# Sheet1.net
KiCad netlist of a schematic drawn in Altium Designer
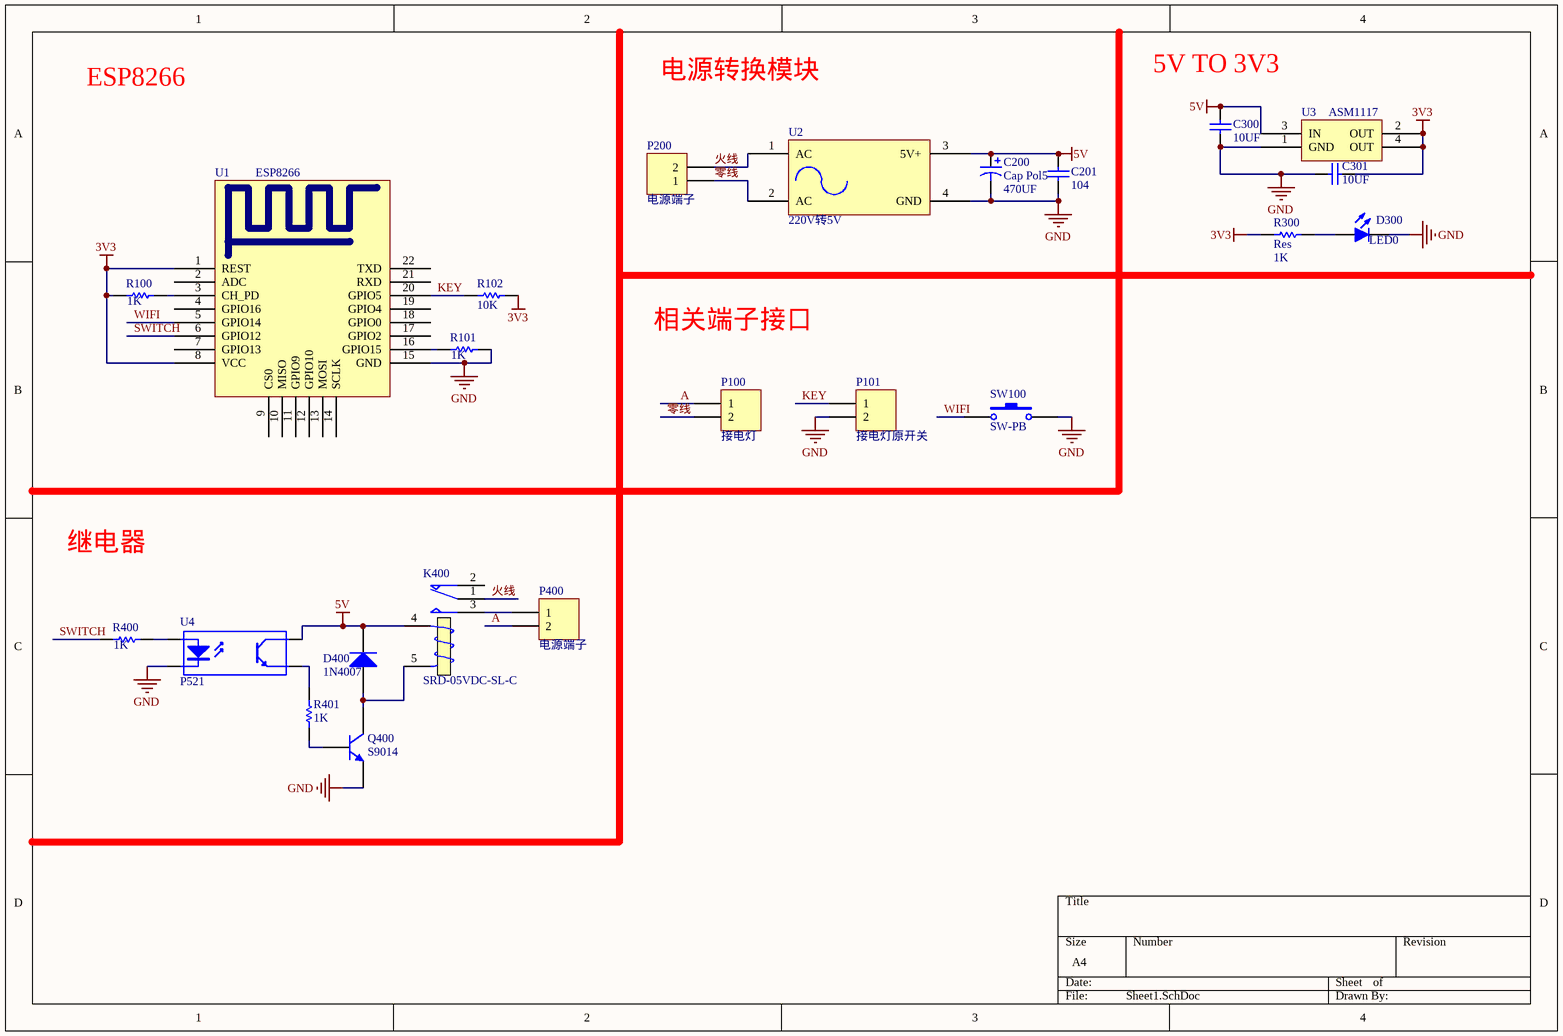
[diagram p0: Sheet1.SchDoc]

(export (version "E")
  (design (tool "Eeschema 10.0.6"))
  (components
    (comp (ref "C200")
      (value "Cap Pol5")
      (footprint "SMD8*10.5")
      (description "220UF电解电容")
      (fields (field (name "VAULE") "470UF"))
      (libsource (lib "myintlib") (part "Cap Pol5"))
    )
    (comp (ref "C201")
      (value "104")
      (footprint "Cap0805")
      (description "0805贴片电容")
      (libsource (lib "myintlib") (part "Cap"))
    )
    (comp (ref "C300")
      (value "10UF")
      (footprint "Cap0805")
      (description "0805贴片电容")
      (libsource (lib "myintlib") (part "Cap"))
    )
    (comp (ref "C301")
      (value "10UF")
      (footprint "Cap0805")
      (description "0805贴片电容")
      (libsource (lib "myintlib") (part "Cap"))
    )
    (comp (ref "D300")
      (value "LED0")
      (footprint "LED-0805")
      (description "0805贴片LED灯")
      (libsource (lib "myintlib") (part "LED0"))
    )
    (comp (ref "D400")
      (value "1N4007")
      (footprint "DO-214AA")
      (description "肖特基二极管")
      (libsource (lib "myintlib") (part "Doide"))
    )
    (comp (ref "K400")
      (value "SRD-05VDC-SL-C")
      (footprint "MODULE5B")
      (description "SPDT Relay")
      (fields (field (name "PUBLISHER") "Altium Limited"))
      (libsource (lib "Miscellaneous Devices") (part "Relay"))
    )
    (comp (ref "P100")
      (value "接电灯")
      (footprint "HDR1X2")
      (description "Header, 2-Pin")
      (fields (field (name "PUBLISHER") "Altium Limited"))
      (libsource (lib "Miscellaneous Connectors") (part "Header 2"))
    )
    (comp (ref "P101")
      (value "接电灯原开关")
      (footprint "HDR1X2")
      (description "Header, 2-Pin")
      (fields (field (name "PUBLISHER") "Altium Limited"))
      (libsource (lib "Miscellaneous Connectors") (part "Header 2"))
    )
    (comp (ref "P200")
      (value "电源端子")
      (footprint "HDR1X2")
      (description "Header, 2-Pin")
      (fields (field (name "PUBLISHER") "Altium Limited"))
      (libsource (lib "") (part "Header 2_1"))
    )
    (comp (ref "P400")
      (value "电源端子")
      (footprint "HDR1X2")
      (description "Header, 2-Pin")
      (fields (field (name "PUBLISHER") "Altium Limited"))
      (libsource (lib "Miscellaneous Connectors") (part "Header 2"))
    )
    (comp (ref "Q400")
      (value "S9014")
      (footprint "TO-226-AA")
      (description "NPN Bipolar Transistor")
      (fields (field (name "PUBLISHER") "Altium Limited"))
      (libsource (lib "Miscellaneous Devices") (part "NPN"))
    )
    (comp (ref "R100")
      (value "Res")
      (footprint "0805")
      (description "0805贴片电阻")
      (fields (field (name "VAULE") "1K"))
      (libsource (lib "myintlib") (part "Res"))
    )
    (comp (ref "R101")
      (value "Res")
      (footprint "0805")
      (description "0805贴片电阻")
      (fields (field (name "VAULE") "1K"))
      (libsource (lib "myintlib") (part "Res"))
    )
    (comp (ref "R102")
      (value "Res")
      (footprint "0805")
      (description "0805贴片电阻")
      (fields (field (name "VAULE") "10K"))
      (libsource (lib "myintlib") (part "Res"))
    )
    (comp (ref "R300")
      (value "Res")
      (footprint "0805")
      (description "0805贴片电阻")
      (fields (field (name "VAULE") "1K"))
      (libsource (lib "myintlib") (part "Res"))
    )
    (comp (ref "R400")
      (value "Res")
      (footprint "0805")
      (description "0805贴片电阻")
      (fields (field (name "VAULE") "1K"))
      (libsource (lib "myintlib") (part "Res"))
    )
    (comp (ref "R401")
      (value "Res")
      (footprint "0805")
      (description "0805贴片电阻")
      (fields (field (name "VAULE") "1K"))
      (libsource (lib "myintlib") (part "Res"))
    )
    (comp (ref "SW100")
      (value "SW-PB")
      (footprint "SW-PB")
      (description "贴片按键")
      (libsource (lib "myintlib") (part "SW-PB"))
    )
    (comp (ref "U1")
      (value "ESP8266")
      (footprint "ESP8266")
      (description "串口wifi模块")
      (libsource (lib "myintlib") (part "ESP8266"))
    )
    (comp (ref "U2") (value "220V转5V") (libsource (lib "myintlib") (part "电源转换")))
    (comp (ref "U3")
      (value "ASM1117")
      (footprint "SOT-223")
      (description "线性稳压芯片")
      (libsource (lib "myintlib") (part "ASM1117"))
    )
    (comp (ref "U4")
      (value "P521")
      (footprint "DIP-4")
      (description "4-Pin Phototransistor Optocoupler")
      (fields (field (name "PUBLISHER") "Altium Limited"))
      (libsource (lib "Miscellaneous Devices") (part "Optoisolator1"))
    )
  )
  (nets
    (net (code "1") (name "/A") (class "Default")
      (node (ref "P100") (pin "1") (pinfunction "1_1") (pintype "passive"))
      (node (ref "P400") (pin "2") (pinfunction "2_2") (pintype "passive"))
    )
    (net (code "2") (name "/KEY") (class "Default")
      (node (ref "P101") (pin "1") (pinfunction "1_1") (pintype "passive"))
      (node (ref "R102") (pin "1") (pinfunction "1_1") (pintype "passive"))
      (node (ref "U1") (pin "20") (pinfunction "GPIO5_20") (pintype "passive"))
    )
    (net (code "3") (name "/SWITCH") (class "Default")
      (node (ref "R400") (pin "1") (pinfunction "1_1") (pintype "passive"))
      (node (ref "U1") (pin "6") (pinfunction "GPIO12_6") (pintype "passive"))
    )
    (net (code "4") (name "/WIFI") (class "Default")
      (node (ref "SW100") (pin "1") (pinfunction "1_1") (pintype "passive"))
      (node (ref "U1") (pin "5") (pinfunction "GPIO14_5") (pintype "passive"))
    )
    (net (code "5") (name "/火线") (class "Default")
      (node (ref "K400") (pin "1") (pinfunction "COM_1") (pintype "passive"))
      (node (ref "P200") (pin "2") (pinfunction "2_2") (pintype "passive"))
      (node (ref "U2") (pin "1") (pinfunction "AC_1") (pintype "passive"))
    )
    (net (code "6") (name "/零线") (class "Default")
      (node (ref "P100") (pin "2") (pinfunction "2_2") (pintype "passive"))
      (node (ref "P200") (pin "1") (pinfunction "1_1") (pintype "passive"))
      (node (ref "U2") (pin "2") (pinfunction "AC_2") (pintype "passive"))
    )
    (net (code "7") (name "3V3") (class "Default")
      (node (ref "C301") (pin "1") (pinfunction "1_1") (pintype "passive"))
      (node (ref "R100") (pin "1") (pinfunction "1_1") (pintype "passive"))
      (node (ref "R102") (pin "2") (pinfunction "2_2") (pintype "passive"))
      (node (ref "R300") (pin "1") (pinfunction "1_1") (pintype "passive"))
      (node (ref "U1") (pin "1") (pinfunction "REST_1") (pintype "passive"))
      (node (ref "U1") (pin "8") (pinfunction "VCC_8") (pintype "passive"))
      (node (ref "U3") (pin "2") (pinfunction "OUT_2") (pintype "passive"))
      (node (ref "U3") (pin "4") (pinfunction "OUT_4") (pintype "passive"))
    )
    (net (code "8") (name "5V") (class "Default")
      (node (ref "C200") (pin "1") (pinfunction "1_1") (pintype "passive"))
      (node (ref "C201") (pin "1") (pinfunction "1_1") (pintype "passive"))
      (node (ref "C300") (pin "2") (pinfunction "2_2") (pintype "passive"))
      (node (ref "D400") (pin "2") (pinfunction "K_2") (pintype "passive"))
      (node (ref "K400") (pin "4") (pinfunction "T1_4") (pintype "passive"))
      (node (ref "U2") (pin "3") (pinfunction "5V+_3") (pintype "passive"))
      (node (ref "U3") (pin "3") (pinfunction "IN_3") (pintype "passive"))
      (node (ref "U4") (pin "4") (pinfunction "C_4") (pintype "passive"))
    )
    (net (code "9") (name "GND") (class "Default")
      (node (ref "C200") (pin "2") (pinfunction "2_2") (pintype "passive"))
      (node (ref "C201") (pin "2") (pinfunction "2_2") (pintype "passive"))
      (node (ref "C300") (pin "1") (pinfunction "1_1") (pintype "passive"))
      (node (ref "C301") (pin "2") (pinfunction "2_2") (pintype "passive"))
      (node (ref "D300") (pin "2") (pinfunction "K_2") (pintype "passive"))
      (node (ref "P101") (pin "2") (pinfunction "2_2") (pintype "passive"))
      (node (ref "Q400") (pin "3") (pinfunction "E_3") (pintype "passive"))
      (node (ref "R101") (pin "2") (pinfunction "2_2") (pintype "passive"))
      (node (ref "SW100") (pin "2") (pinfunction "2_2") (pintype "passive"))
      (node (ref "U1") (pin "15") (pinfunction "GND_15") (pintype "passive"))
      (node (ref "U2") (pin "4") (pinfunction "GND_4") (pintype "passive"))
      (node (ref "U3") (pin "1") (pinfunction "GND_1") (pintype "passive"))
      (node (ref "U4") (pin "2") (pinfunction "K_2") (pintype "passive"))
    )
    (net (code "10") (name "Net-(D300-A)") (class "Default")
      (node (ref "D300") (pin "1") (pinfunction "A_1") (pintype "passive"))
      (node (ref "R300") (pin "2") (pinfunction "2_2") (pintype "passive"))
    )
    (net (code "11") (name "Net-(D400-A)") (class "Default")
      (node (ref "D400") (pin "1") (pinfunction "A_1") (pintype "passive"))
      (node (ref "K400") (pin "5") (pinfunction "T2_5") (pintype "passive"))
      (node (ref "Q400") (pin "1") (pinfunction "C_1") (pintype "passive"))
    )
    (net (code "12") (name "Net-(K400-NO)") (class "Default")
      (node (ref "K400") (pin "3") (pinfunction "NO_3") (pintype "passive"))
      (node (ref "P400") (pin "1") (pinfunction "1_1") (pintype "passive"))
    )
    (net (code "13") (name "Net-(Q400-B)") (class "Default")
      (node (ref "Q400") (pin "2") (pinfunction "B_2") (pintype "passive"))
      (node (ref "R401") (pin "1") (pinfunction "1_1") (pintype "passive"))
    )
    (net (code "14") (name "Net-(U1-CH_PD)") (class "Default")
      (node (ref "R100") (pin "2") (pinfunction "2_2") (pintype "passive"))
      (node (ref "U1") (pin "3") (pinfunction "CH_PD_3") (pintype "passive"))
    )
    (net (code "15") (name "Net-(U1-GPIO15)") (class "Default")
      (node (ref "R101") (pin "1") (pinfunction "1_1") (pintype "passive"))
      (node (ref "U1") (pin "16") (pinfunction "GPIO15_16") (pintype "passive"))
    )
    (net (code "16") (name "Net-(U4-A)") (class "Default")
      (node (ref "R400") (pin "2") (pinfunction "2_2") (pintype "passive"))
      (node (ref "U4") (pin "1") (pinfunction "A_1") (pintype "passive"))
    )
    (net (code "17") (name "Net-(U4-E)") (class "Default")
      (node (ref "R401") (pin "2") (pinfunction "2_2") (pintype "passive"))
      (node (ref "U4") (pin "3") (pinfunction "E_3") (pintype "passive"))
    )
    (net (code "18") (name "unconnected-(K400-NC-Pad2)") (class "Default")
      (node (ref "K400") (pin "2") (pinfunction "NC_2") (pintype "passive"))
    )
    (net (code "19") (name "unconnected-(U1-ADC-Pad2)") (class "Default")
      (node (ref "U1") (pin "2") (pinfunction "ADC_2") (pintype "passive"))
    )
    (net (code "20") (name "unconnected-(U1-CS0-Pad9)") (class "Default")
      (node (ref "U1") (pin "9") (pinfunction "CS0_9") (pintype "passive"))
    )
    (net (code "21") (name "unconnected-(U1-GPIO0-Pad18)") (class "Default")
      (node (ref "U1") (pin "18") (pinfunction "GPIO0_18") (pintype "passive"))
    )
    (net (code "22") (name "unconnected-(U1-GPIO2-Pad17)") (class "Default")
      (node (ref "U1") (pin "17") (pinfunction "GPIO2_17") (pintype "passive"))
    )
    (net (code "23") (name "unconnected-(U1-GPIO4-Pad19)") (class "Default")
      (node (ref "U1") (pin "19") (pinfunction "GPIO4_19") (pintype "passive"))
    )
    (net (code "24") (name "unconnected-(U1-GPIO9-Pad11)") (class "Default")
      (node (ref "U1") (pin "11") (pinfunction "GPIO9_11") (pintype "passive"))
    )
    (net (code "25") (name "unconnected-(U1-GPIO10-Pad12)") (class "Default")
      (node (ref "U1") (pin "12") (pinfunction "GPIO10_12") (pintype "passive"))
    )
    (net (code "26") (name "unconnected-(U1-GPIO13-Pad7)") (class "Default")
      (node (ref "U1") (pin "7") (pinfunction "GPIO13_7") (pintype "passive"))
    )
    (net (code "27") (name "unconnected-(U1-GPIO16-Pad4)") (class "Default")
      (node (ref "U1") (pin "4") (pinfunction "GPIO16_4") (pintype "passive"))
    )
    (net (code "28") (name "unconnected-(U1-MISO-Pad10)") (class "Default")
      (node (ref "U1") (pin "10") (pinfunction "MISO_10") (pintype "passive"))
    )
    (net (code "29") (name "unconnected-(U1-MOSI-Pad13)") (class "Default")
      (node (ref "U1") (pin "13") (pinfunction "MOSI_13") (pintype "passive"))
    )
    (net (code "30") (name "unconnected-(U1-RXD-Pad21)") (class "Default")
      (node (ref "U1") (pin "21") (pinfunction "RXD_21") (pintype "passive"))
    )
    (net (code "31") (name "unconnected-(U1-SCLK-Pad14)") (class "Default")
      (node (ref "U1") (pin "14") (pinfunction "SCLK_14") (pintype "passive"))
    )
    (net (code "32") (name "unconnected-(U1-TXD-Pad22)") (class "Default")
      (node (ref "U1") (pin "22") (pinfunction "TXD_22") (pintype "passive"))
    )
  )
)
